# SD_Card_Adapter.net
KiCad netlist of a schematic drawn in Altium Designer
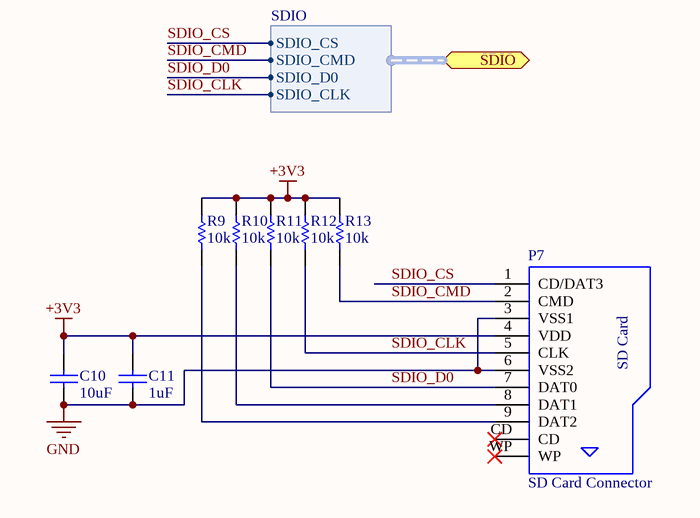
[diagram p0: SD_Card_Adapter.SchDoc]

(export (version "E")
  (design (tool "Eeschema 10.0.6"))
  (components
    (comp (ref "C10")
      (value "10uF")
      (footprint "CAP_0805_IPC_MD")
      (description "Capacitor")
      (fields (field (name "MANUFACTURER") "Sansung") (field (name "Comment") "Cap"))
      (libsource (lib "DataLogger") (part "Cap"))
    )
    (comp (ref "C11")
      (value "1uF")
      (footprint "CAP_0805_IPC_MD")
      (description "Capacitor")
      (fields (field (name "MANUFACTURER") "Samsung") (field (name "Comment") "Cap"))
      (libsource (lib "DataLogger") (part "Cap"))
    )
    (comp (ref "P7")
      (value "SD Card Connector")
      (footprint "693061010911")
      (description "WR-CRD SD_Push and Push")
      (fields
        (field (name "MANUFACTURER") "W¨ąrth Elektronik eiSos GmbH")
        (field (name "PARTNO") "693061010911")
        (field (name "CREATED BY") "Karrer Zheng")
      )
      (libsource (lib "DataLogger") (part "SD Card Connector"))
    )
    (comp (ref "R9")
      (value "10k")
      (footprint "RES_0805_IPC_MD")
      (description "Resistor")
      (fields (field (name "Comment") "Res"))
      (libsource (lib "DataLogger") (part "Res"))
    )
    (comp (ref "R10")
      (value "10k")
      (footprint "RES_0805_IPC_MD")
      (description "Resistor")
      (fields (field (name "Comment") "Res"))
      (libsource (lib "DataLogger") (part "Res"))
    )
    (comp (ref "R11")
      (value "10k")
      (footprint "RES_0805_IPC_MD")
      (description "Resistor")
      (fields (field (name "Comment") "Res"))
      (libsource (lib "DataLogger") (part "Res"))
    )
    (comp (ref "R12")
      (value "10k")
      (footprint "RES_0805_IPC_MD")
      (description "Resistor")
      (fields (field (name "Comment") "Res"))
      (libsource (lib "DataLogger") (part "Res"))
    )
    (comp (ref "R13")
      (value "10k")
      (footprint "RES_0805_IPC_MD")
      (description "Resistor")
      (fields (field (name "Comment") "Res"))
      (libsource (lib "DataLogger") (part "Res"))
    )
  )
  (nets
    (net (code "2") (name "+3V3") (class "Default")
      (node (ref "C10") (pin "2") (pinfunction "2_2") (pintype "passive"))
      (node (ref "C11") (pin "2") (pinfunction "2_2") (pintype "passive"))
      (node (ref "P7") (pin "4") (pinfunction "VDD_4") (pintype "power_in"))
      (node (ref "R10") (pin "2") (pinfunction "2_2") (pintype "passive"))
      (node (ref "R11") (pin "2") (pinfunction "2_2") (pintype "passive"))
      (node (ref "R12") (pin "2") (pinfunction "2_2") (pintype "passive"))
      (node (ref "R13") (pin "2") (pinfunction "2_2") (pintype "passive"))
      (node (ref "R9") (pin "2") (pinfunction "2_2") (pintype "passive"))
    )
    (net (code "3") (name "/SDIO_CLK") (class "Default")
      (node (ref "P7") (pin "5") (pinfunction "CLK_5") (pintype "passive"))
      (node (ref "R12") (pin "1") (pinfunction "1_1") (pintype "passive"))
    )
    (net (code "4") (name "/SDIO_CMD") (class "Default")
      (node (ref "P7") (pin "2") (pinfunction "CMD_2") (pintype "passive"))
      (node (ref "R13") (pin "1") (pinfunction "1_1") (pintype "passive"))
    )
    (net (code "5") (name "/SDIO_CS") (class "Default")
      (node (ref "P7") (pin "1") (pinfunction "CD/DAT3_1") (pintype "passive"))
    )
    (net (code "6") (name "/SDIO_D0") (class "Default")
      (node (ref "P7") (pin "7") (pinfunction "DAT0_7") (pintype "passive"))
      (node (ref "R11") (pin "1") (pinfunction "1_1") (pintype "passive"))
    )
    (net (code "8") (name "GND") (class "Default")
      (node (ref "C10") (pin "1") (pinfunction "1_1") (pintype "passive"))
      (node (ref "C11") (pin "1") (pinfunction "1_1") (pintype "passive"))
      (node (ref "P7") (pin "3") (pinfunction "VSS1_3") (pintype "power_in"))
      (node (ref "P7") (pin "6") (pinfunction "VSS2_6") (pintype "power_in"))
    )
    (net (code "9") (name "Net-(P7-DAT1)") (class "Default")
      (node (ref "P7") (pin "8") (pinfunction "DAT1_8") (pintype "passive"))
      (node (ref "R10") (pin "1") (pinfunction "1_1") (pintype "passive"))
    )
    (net (code "10") (name "Net-(P7-DAT2)") (class "Default")
      (node (ref "P7") (pin "9") (pinfunction "DAT2_9") (pintype "passive"))
      (node (ref "R9") (pin "1") (pinfunction "1_1") (pintype "passive"))
    )
    (net (code "11") (name "unconnected-(P7-PadCD)") (class "Default")
      (node (ref "P7") (pin "CD") (pinfunction "CD_CD") (pintype "passive+no_connect"))
    )
    (net (code "12") (name "unconnected-(P7-PadWP)") (class "Default")
      (node (ref "P7") (pin "WP") (pinfunction "WP_WP") (pintype "passive+no_connect"))
    )
  )
)
